# CP2526_TOUCH.net
KiCad netlist of a schematic drawn in Altium Designer
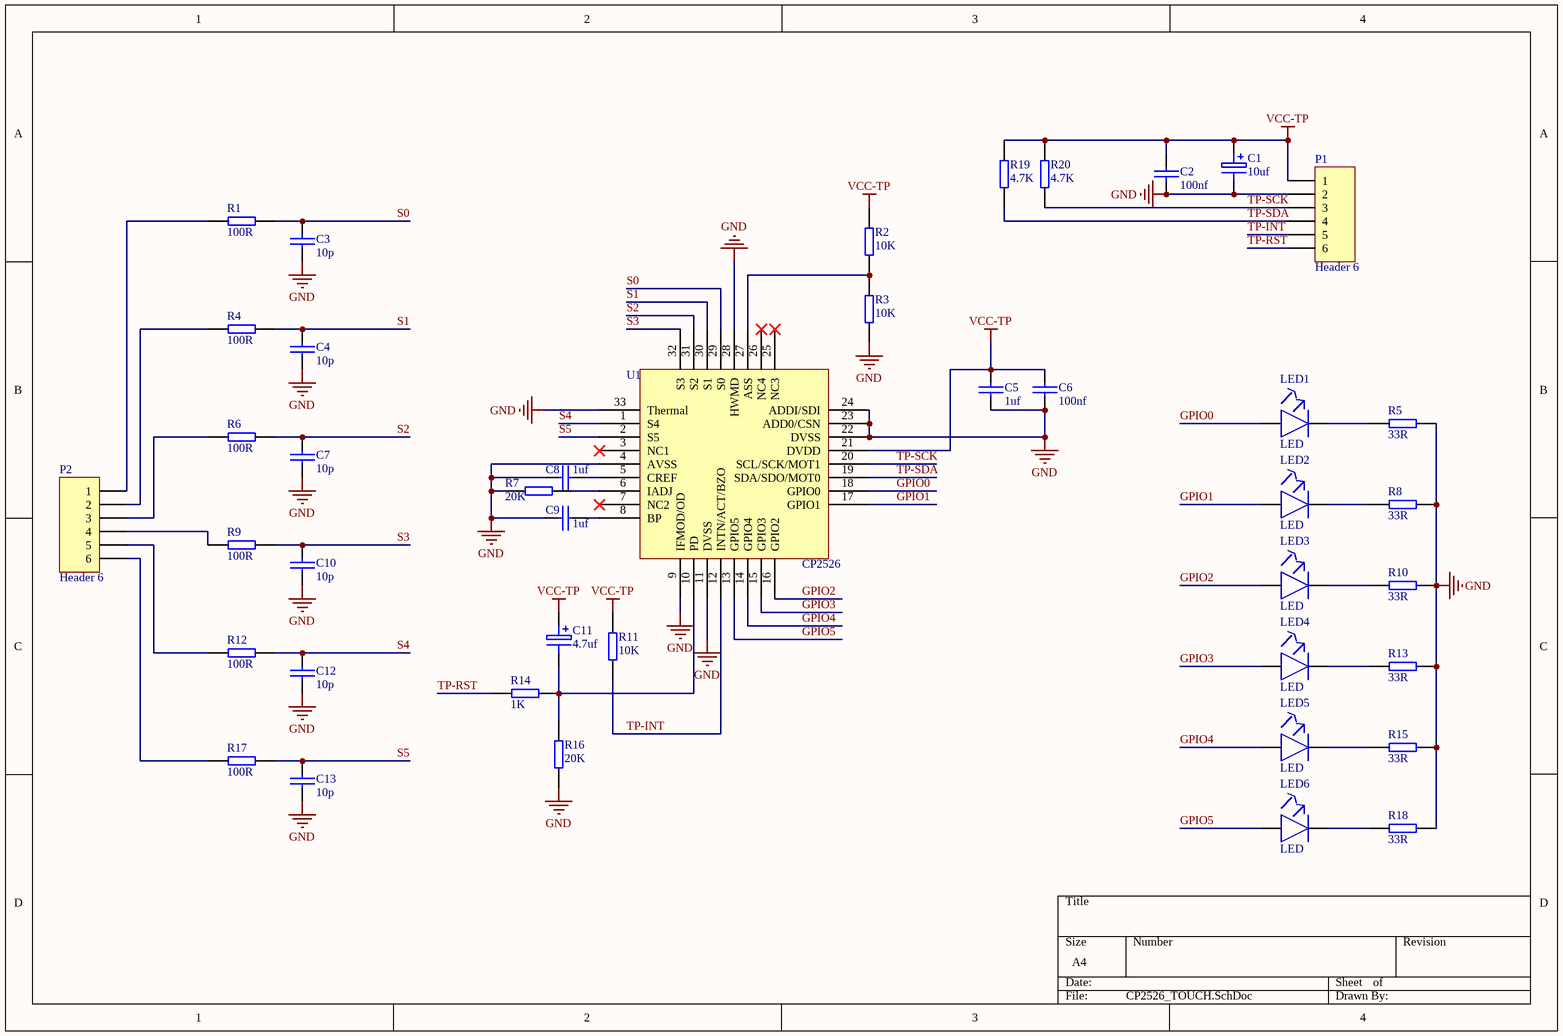
[diagram p0: CP2526_TOUCH.SchDoc]

(export (version "E")
  (design (tool "Eeschema 10.0.6"))
  (components
    (comp (ref "C1")
      (value "10uf")
      (footprint "1206-C")
      (description "Electrolytic Capacitor")
      (libsource (lib "JHTSCH") (part "CAP2"))
    )
    (comp (ref "C2")
      (value "100nf")
      (footprint "0603")
      (description "Capacitor")
      (libsource (lib "JHTSCH") (part "CAP"))
    )
    (comp (ref "C3")
      (value "10p")
      (footprint "0603")
      (description "Capacitor")
      (libsource (lib "JHTSCH") (part "CAP"))
    )
    (comp (ref "C4")
      (value "10p")
      (footprint "0603")
      (description "Capacitor")
      (libsource (lib "JHTSCH") (part "CAP"))
    )
    (comp (ref "C5")
      (value "1uf")
      (footprint "0603")
      (description "Capacitor")
      (libsource (lib "JHTSCH") (part "CAP"))
    )
    (comp (ref "C6")
      (value "100nf")
      (footprint "0603")
      (description "Capacitor")
      (libsource (lib "JHTSCH") (part "CAP"))
    )
    (comp (ref "C7")
      (value "10p")
      (footprint "0603")
      (description "Capacitor")
      (libsource (lib "JHTSCH") (part "CAP"))
    )
    (comp (ref "C8")
      (value "1uf")
      (footprint "0603")
      (description "Capacitor")
      (libsource (lib "JHTSCH") (part "CAP"))
    )
    (comp (ref "C9")
      (value "1uf")
      (footprint "0603")
      (description "Capacitor")
      (libsource (lib "JHTSCH") (part "CAP"))
    )
    (comp (ref "C10")
      (value "10p")
      (footprint "0603")
      (description "Capacitor")
      (libsource (lib "JHTSCH") (part "CAP"))
    )
    (comp (ref "C11")
      (value "4.7uf")
      (footprint "1206-C")
      (description "Electrolytic Capacitor")
      (libsource (lib "JHTSCH") (part "CAP2"))
    )
    (comp (ref "C12")
      (value "10p")
      (footprint "0603")
      (description "Capacitor")
      (libsource (lib "JHTSCH") (part "CAP"))
    )
    (comp (ref "C13")
      (value "10p")
      (footprint "0603")
      (description "Capacitor")
      (libsource (lib "JHTSCH") (part "CAP"))
    )
    (comp (ref "LED1") (value "LED") (footprint "0603") (libsource (lib "JHTSCH") (part "LED")))
    (comp (ref "LED2") (value "LED") (footprint "0603") (libsource (lib "JHTSCH") (part "LED")))
    (comp (ref "LED3") (value "LED") (footprint "0603") (libsource (lib "JHTSCH") (part "LED")))
    (comp (ref "LED4") (value "LED") (footprint "0603") (libsource (lib "JHTSCH") (part "LED")))
    (comp (ref "LED5") (value "LED") (footprint "0603") (libsource (lib "JHTSCH") (part "LED")))
    (comp (ref "LED6") (value "LED") (footprint "0603") (libsource (lib "JHTSCH") (part "LED")))
    (comp (ref "P1")
      (value "Header 6")
      (footprint "HDR1X6")
      (description "Header, 6-Pin")
      (fields (field (name "PUBLISHER") "Altium Limited"))
      (libsource (lib "") (part "Header 6_1"))
    )
    (comp (ref "P2")
      (value "Header 6")
      (footprint "HDR1X6")
      (description "Header, 6-Pin")
      (fields (field (name "PUBLISHER") "Altium Limited"))
      (libsource (lib "Miscellaneous Connectors") (part "Header 6"))
    )
    (comp (ref "R1") (value "100R") (footprint "0603") (libsource (lib "JHTSCH") (part "RES2")))
    (comp (ref "R2") (value "10K") (footprint "0603") (libsource (lib "JHTSCH") (part "RES2")))
    (comp (ref "R3") (value "10K") (footprint "0603") (libsource (lib "JHTSCH") (part "RES2")))
    (comp (ref "R4") (value "100R") (footprint "0603") (libsource (lib "JHTSCH") (part "RES2")))
    (comp (ref "R5") (value "33R") (footprint "0603") (libsource (lib "JHTSCH") (part "RES2")))
    (comp (ref "R6") (value "100R") (footprint "0603") (libsource (lib "JHTSCH") (part "RES2")))
    (comp (ref "R7") (value "20K") (footprint "0603") (libsource (lib "JHTSCH") (part "RES2")))
    (comp (ref "R8") (value "33R") (footprint "0603") (libsource (lib "JHTSCH") (part "RES2")))
    (comp (ref "R9") (value "100R") (footprint "0603") (libsource (lib "JHTSCH") (part "RES2")))
    (comp (ref "R10") (value "33R") (footprint "0603") (libsource (lib "JHTSCH") (part "RES2")))
    (comp (ref "R11") (value "10K") (footprint "0603") (libsource (lib "JHTSCH") (part "RES2")))
    (comp (ref "R12") (value "100R") (footprint "0603") (libsource (lib "JHTSCH") (part "RES2")))
    (comp (ref "R13") (value "33R") (footprint "0603") (libsource (lib "JHTSCH") (part "RES2")))
    (comp (ref "R14") (value "1K") (footprint "0603") (libsource (lib "JHTSCH") (part "RES2")))
    (comp (ref "R15") (value "33R") (footprint "0603") (libsource (lib "JHTSCH") (part "RES2")))
    (comp (ref "R16") (value "20K") (footprint "0603") (libsource (lib "JHTSCH") (part "RES2")))
    (comp (ref "R17") (value "100R") (footprint "0603") (libsource (lib "JHTSCH") (part "RES2")))
    (comp (ref "R18") (value "33R") (footprint "0603") (libsource (lib "JHTSCH") (part "RES2")))
    (comp (ref "R19") (value "4.7K") (footprint "0603") (libsource (lib "JHTSCH") (part "RES2")))
    (comp (ref "R20") (value "4.7K") (footprint "0603") (libsource (lib "JHTSCH") (part "RES2")))
    (comp (ref "U1") (value "CP2526") (footprint "LQFP32") (libsource (lib "JHTSCH") (part "CP2526")))
  )
  (nets
    (net (code "1") (name "/GPIO0") (class "Default")
      (node (ref "LED1") (pin "1") (pinfunction "+_1") (pintype "passive"))
      (node (ref "U1") (pin "18") (pinfunction "GPIO0_18") (pintype "passive"))
    )
    (net (code "2") (name "/GPIO1") (class "Default")
      (node (ref "LED2") (pin "1") (pinfunction "+_1") (pintype "passive"))
      (node (ref "U1") (pin "17") (pinfunction "GPIO1_17") (pintype "passive"))
    )
    (net (code "3") (name "/GPIO2") (class "Default")
      (node (ref "LED3") (pin "1") (pinfunction "+_1") (pintype "passive"))
      (node (ref "U1") (pin "16") (pinfunction "GPIO2_16") (pintype "passive"))
    )
    (net (code "4") (name "/GPIO3") (class "Default")
      (node (ref "LED4") (pin "1") (pinfunction "+_1") (pintype "passive"))
      (node (ref "U1") (pin "15") (pinfunction "GPIO3_15") (pintype "passive"))
    )
    (net (code "5") (name "/GPIO4") (class "Default")
      (node (ref "LED5") (pin "1") (pinfunction "+_1") (pintype "passive"))
      (node (ref "U1") (pin "14") (pinfunction "GPIO4_14") (pintype "passive"))
    )
    (net (code "6") (name "/GPIO5") (class "Default")
      (node (ref "LED6") (pin "1") (pinfunction "+_1") (pintype "passive"))
      (node (ref "U1") (pin "13") (pinfunction "GPIO5_13") (pintype "passive"))
    )
    (net (code "7") (name "/S0") (class "Default")
      (node (ref "C3") (pin "1") (pinfunction "1_1") (pintype "passive"))
      (node (ref "R1") (pin "2") (pinfunction "2_2") (pintype "passive"))
      (node (ref "U1") (pin "29") (pinfunction "S0_29") (pintype "passive"))
    )
    (net (code "8") (name "/S1") (class "Default")
      (node (ref "C4") (pin "1") (pinfunction "1_1") (pintype "passive"))
      (node (ref "R4") (pin "2") (pinfunction "2_2") (pintype "passive"))
      (node (ref "U1") (pin "30") (pinfunction "S1_30") (pintype "passive"))
    )
    (net (code "9") (name "/S2") (class "Default")
      (node (ref "C7") (pin "1") (pinfunction "1_1") (pintype "passive"))
      (node (ref "R6") (pin "2") (pinfunction "2_2") (pintype "passive"))
      (node (ref "U1") (pin "31") (pinfunction "S2_31") (pintype "passive"))
    )
    (net (code "10") (name "/S3") (class "Default")
      (node (ref "C10") (pin "1") (pinfunction "1_1") (pintype "passive"))
      (node (ref "R9") (pin "2") (pinfunction "2_2") (pintype "passive"))
      (node (ref "U1") (pin "32") (pinfunction "S3_32") (pintype "passive"))
    )
    (net (code "11") (name "/S4") (class "Default")
      (node (ref "C12") (pin "1") (pinfunction "1_1") (pintype "passive"))
      (node (ref "R12") (pin "2") (pinfunction "2_2") (pintype "passive"))
      (node (ref "U1") (pin "1") (pinfunction "S4_1") (pintype "passive"))
    )
    (net (code "12") (name "/S5") (class "Default")
      (node (ref "C13") (pin "1") (pinfunction "1_1") (pintype "passive"))
      (node (ref "R17") (pin "2") (pinfunction "2_2") (pintype "passive"))
      (node (ref "U1") (pin "2") (pinfunction "S5_2") (pintype "passive"))
    )
    (net (code "13") (name "/TP-INT") (class "Default")
      (node (ref "P1") (pin "5") (pinfunction "5_5") (pintype "passive"))
      (node (ref "R11") (pin "1") (pinfunction "1_1") (pintype "passive"))
      (node (ref "U1") (pin "12") (pinfunction "INTN/ACT/BZO_12") (pintype "passive"))
    )
    (net (code "14") (name "/TP-RST") (class "Default")
      (node (ref "P1") (pin "6") (pinfunction "6_6") (pintype "passive"))
      (node (ref "R14") (pin "1") (pinfunction "1_1") (pintype "passive"))
    )
    (net (code "15") (name "/TP-SCK") (class "Default")
      (node (ref "P1") (pin "3") (pinfunction "3_3") (pintype "passive"))
      (node (ref "R20") (pin "1") (pinfunction "1_1") (pintype "passive"))
      (node (ref "U1") (pin "20") (pinfunction "SCL/SCK/MOT1_20") (pintype "passive"))
    )
    (net (code "16") (name "/TP-SDA") (class "Default")
      (node (ref "P1") (pin "4") (pinfunction "4_4") (pintype "passive"))
      (node (ref "R19") (pin "1") (pinfunction "1_1") (pintype "passive"))
      (node (ref "U1") (pin "19") (pinfunction "SDA/SDO/MOT0_19") (pintype "passive"))
    )
    (net (code "17") (name "GND") (class "Default")
      (node (ref "C1") (pin "2") (pinfunction "2_2") (pintype "passive"))
      (node (ref "C10") (pin "2") (pinfunction "2_2") (pintype "passive"))
      (node (ref "C12") (pin "2") (pinfunction "2_2") (pintype "passive"))
      (node (ref "C13") (pin "2") (pinfunction "2_2") (pintype "passive"))
      (node (ref "C2") (pin "2") (pinfunction "2_2") (pintype "passive"))
      (node (ref "C3") (pin "2") (pinfunction "2_2") (pintype "passive"))
      (node (ref "C4") (pin "2") (pinfunction "2_2") (pintype "passive"))
      (node (ref "C5") (pin "2") (pinfunction "2_2") (pintype "passive"))
      (node (ref "C6") (pin "2") (pinfunction "2_2") (pintype "passive"))
      (node (ref "C7") (pin "2") (pinfunction "2_2") (pintype "passive"))
      (node (ref "C8") (pin "1") (pinfunction "1_1") (pintype "passive"))
      (node (ref "C9") (pin "1") (pinfunction "1_1") (pintype "passive"))
      (node (ref "P1") (pin "2") (pinfunction "2_2") (pintype "passive"))
      (node (ref "R10") (pin "2") (pinfunction "2_2") (pintype "passive"))
      (node (ref "R13") (pin "2") (pinfunction "2_2") (pintype "passive"))
      (node (ref "R15") (pin "2") (pinfunction "2_2") (pintype "passive"))
      (node (ref "R16") (pin "1") (pinfunction "1_1") (pintype "passive"))
      (node (ref "R18") (pin "2") (pinfunction "2_2") (pintype "passive"))
      (node (ref "R3") (pin "1") (pinfunction "1_1") (pintype "passive"))
      (node (ref "R5") (pin "2") (pinfunction "2_2") (pintype "passive"))
      (node (ref "R7") (pin "1") (pinfunction "1_1") (pintype "passive"))
      (node (ref "R8") (pin "2") (pinfunction "2_2") (pintype "passive"))
      (node (ref "U1") (pin "11") (pinfunction "DVSS_11") (pintype "passive"))
      (node (ref "U1") (pin "22") (pinfunction "DVSS_22") (pintype "passive"))
      (node (ref "U1") (pin "23") (pinfunction "ADD0/CSN_23") (pintype "passive"))
      (node (ref "U1") (pin "24") (pinfunction "ADDI/SDI_24") (pintype "passive"))
      (node (ref "U1") (pin "28") (pinfunction "HWMD_28") (pintype "passive"))
      (node (ref "U1") (pin "33") (pinfunction "Thermal_33") (pintype "passive"))
      (node (ref "U1") (pin "4") (pinfunction "AVSS_4") (pintype "passive"))
      (node (ref "U1") (pin "9") (pinfunction "IFMOD/OD_9") (pintype "passive"))
    )
    (net (code "18") (name "Net-(LED1--)") (class "Default")
      (node (ref "LED1") (pin "2") (pinfunction "-_2") (pintype "passive"))
      (node (ref "R5") (pin "1") (pinfunction "1_1") (pintype "passive"))
    )
    (net (code "19") (name "Net-(LED2--)") (class "Default")
      (node (ref "LED2") (pin "2") (pinfunction "-_2") (pintype "passive"))
      (node (ref "R8") (pin "1") (pinfunction "1_1") (pintype "passive"))
    )
    (net (code "20") (name "Net-(LED3--)") (class "Default")
      (node (ref "LED3") (pin "2") (pinfunction "-_2") (pintype "passive"))
      (node (ref "R10") (pin "1") (pinfunction "1_1") (pintype "passive"))
    )
    (net (code "21") (name "Net-(LED4--)") (class "Default")
      (node (ref "LED4") (pin "2") (pinfunction "-_2") (pintype "passive"))
      (node (ref "R13") (pin "1") (pinfunction "1_1") (pintype "passive"))
    )
    (net (code "22") (name "Net-(LED5--)") (class "Default")
      (node (ref "LED5") (pin "2") (pinfunction "-_2") (pintype "passive"))
      (node (ref "R15") (pin "1") (pinfunction "1_1") (pintype "passive"))
    )
    (net (code "23") (name "Net-(LED6--)") (class "Default")
      (node (ref "LED6") (pin "2") (pinfunction "-_2") (pintype "passive"))
      (node (ref "R18") (pin "1") (pinfunction "1_1") (pintype "passive"))
    )
    (net (code "24") (name "Net-(P2-Pad1)") (class "Default")
      (node (ref "P2") (pin "1") (pinfunction "1_1") (pintype "passive"))
      (node (ref "R1") (pin "1") (pinfunction "1_1") (pintype "passive"))
    )
    (net (code "25") (name "Net-(P2-Pad2)") (class "Default")
      (node (ref "P2") (pin "2") (pinfunction "2_2") (pintype "passive"))
      (node (ref "R4") (pin "1") (pinfunction "1_1") (pintype "passive"))
    )
    (net (code "26") (name "Net-(P2-Pad3)") (class "Default")
      (node (ref "P2") (pin "3") (pinfunction "3_3") (pintype "passive"))
      (node (ref "R6") (pin "1") (pinfunction "1_1") (pintype "passive"))
    )
    (net (code "27") (name "Net-(P2-Pad4)") (class "Default")
      (node (ref "P2") (pin "4") (pinfunction "4_4") (pintype "passive"))
      (node (ref "R9") (pin "1") (pinfunction "1_1") (pintype "passive"))
    )
    (net (code "28") (name "Net-(P2-Pad5)") (class "Default")
      (node (ref "P2") (pin "5") (pinfunction "5_5") (pintype "passive"))
      (node (ref "R12") (pin "1") (pinfunction "1_1") (pintype "passive"))
    )
    (net (code "29") (name "Net-(P2-Pad6)") (class "Default")
      (node (ref "P2") (pin "6") (pinfunction "6_6") (pintype "passive"))
      (node (ref "R17") (pin "1") (pinfunction "1_1") (pintype "passive"))
    )
    (net (code "30") (name "Net-(U1-ASS)") (class "Default")
      (node (ref "R2") (pin "1") (pinfunction "1_1") (pintype "passive"))
      (node (ref "R3") (pin "2") (pinfunction "2_2") (pintype "passive"))
      (node (ref "U1") (pin "27") (pinfunction "ASS_27") (pintype "passive"))
    )
    (net (code "31") (name "Net-(U1-BP)") (class "Default")
      (node (ref "C9") (pin "2") (pinfunction "2_2") (pintype "passive"))
      (node (ref "U1") (pin "8") (pinfunction "BP_8") (pintype "passive"))
    )
    (net (code "32") (name "Net-(U1-CREF)") (class "Default")
      (node (ref "C8") (pin "2") (pinfunction "2_2") (pintype "passive"))
      (node (ref "U1") (pin "5") (pinfunction "CREF_5") (pintype "passive"))
    )
    (net (code "33") (name "Net-(U1-IADJ)") (class "Default")
      (node (ref "R7") (pin "2") (pinfunction "2_2") (pintype "passive"))
      (node (ref "U1") (pin "6") (pinfunction "IADJ_6") (pintype "passive"))
    )
    (net (code "34") (name "Net-(U1-PD)") (class "Default")
      (node (ref "C11") (pin "2") (pinfunction "2_2") (pintype "passive"))
      (node (ref "R14") (pin "2") (pinfunction "2_2") (pintype "passive"))
      (node (ref "R16") (pin "2") (pinfunction "2_2") (pintype "passive"))
      (node (ref "U1") (pin "10") (pinfunction "PD_10") (pintype "passive"))
    )
    (net (code "35") (name "VCC-TP") (class "Default")
      (node (ref "C1") (pin "1") (pinfunction "1_1") (pintype "passive"))
      (node (ref "C11") (pin "1") (pinfunction "1_1") (pintype "passive"))
      (node (ref "C2") (pin "1") (pinfunction "1_1") (pintype "passive"))
      (node (ref "C5") (pin "1") (pinfunction "1_1") (pintype "passive"))
      (node (ref "C6") (pin "1") (pinfunction "1_1") (pintype "passive"))
      (node (ref "P1") (pin "1") (pinfunction "1_1") (pintype "passive"))
      (node (ref "R11") (pin "2") (pinfunction "2_2") (pintype "passive"))
      (node (ref "R19") (pin "2") (pinfunction "2_2") (pintype "passive"))
      (node (ref "R2") (pin "2") (pinfunction "2_2") (pintype "passive"))
      (node (ref "R20") (pin "2") (pinfunction "2_2") (pintype "passive"))
      (node (ref "U1") (pin "21") (pinfunction "DVDD_21") (pintype "passive"))
    )
    (net (code "36") (name "unconnected-(U1-NC1-Pad3)") (class "Default")
      (node (ref "U1") (pin "3") (pinfunction "NC1_3") (pintype "passive+no_connect"))
    )
    (net (code "37") (name "unconnected-(U1-NC2-Pad7)") (class "Default")
      (node (ref "U1") (pin "7") (pinfunction "NC2_7") (pintype "passive+no_connect"))
    )
    (net (code "38") (name "unconnected-(U1-NC3-Pad25)") (class "Default")
      (node (ref "U1") (pin "25") (pinfunction "NC3_25") (pintype "passive+no_connect"))
    )
    (net (code "39") (name "unconnected-(U1-NC4-Pad26)") (class "Default")
      (node (ref "U1") (pin "26") (pinfunction "NC4_26") (pintype "passive+no_connect"))
    )
  )
)
